# Controle1.net
KiCad netlist of a schematic drawn in Altium Designer
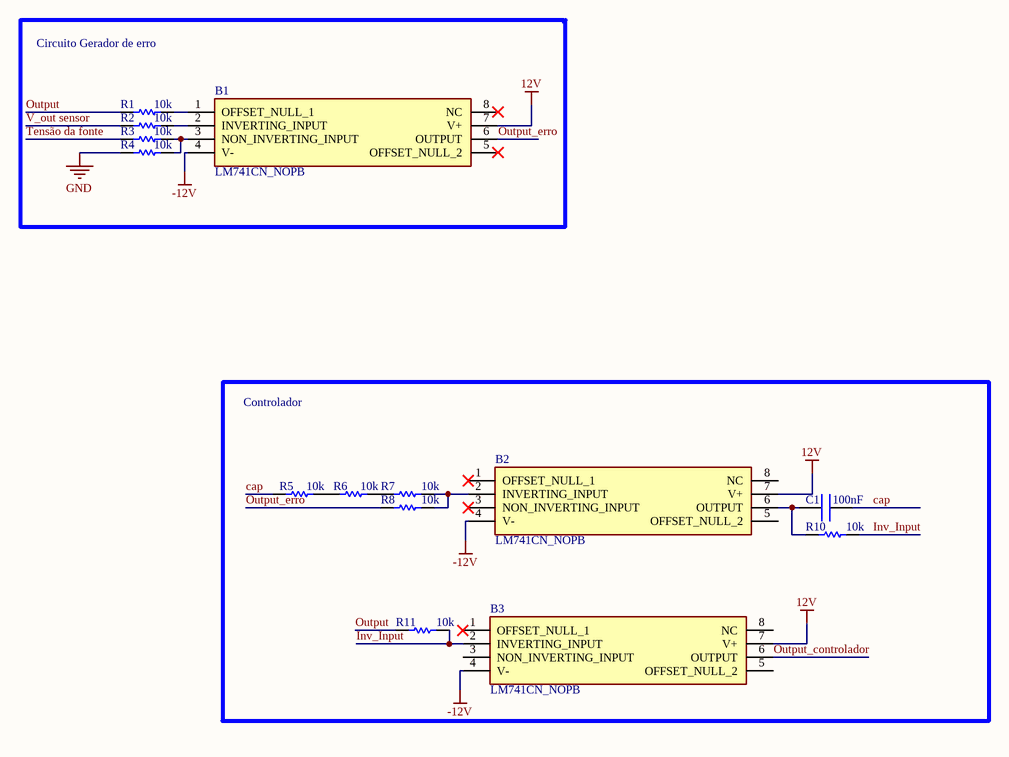
[diagram p0: Controle1.SchDoc]

(export (version "E")
  (design (tool "Eeschema 10.0.6"))
  (components
    (comp (ref "B1")
      (value "LM741CN_NOPB")
      (footprint "DIP794W53P254L959H508Q8N")
      (description "LM741 Operational Amplifier 1MHz DIP8 Texas Instruments LM741CN/NOPB Op Amp, 1MHz, 8-Pin MDIP")
      (fields
        (field (name "MOUSER PART NUMBER") "926-LM741CN/NOPB")
        (field (name "MANUFACTURER_PART_NUMBER") "LM741CN/NOPB")
      )
      (libsource (lib "altium-import") (part "root_0_LM741CN_NOPB_"))
    )
    (comp (ref "B2")
      (value "LM741CN_NOPB")
      (footprint "DIP794W53P254L959H508Q8N")
      (description "LM741 Operational Amplifier 1MHz DIP8 Texas Instruments LM741CN/NOPB Op Amp, 1MHz, 8-Pin MDIP")
      (fields
        (field (name "MOUSER PART NUMBER") "926-LM741CN/NOPB")
        (field (name "MANUFACTURER_PART_NUMBER") "LM741CN/NOPB")
      )
      (libsource (lib "altium-import") (part "root_0_LM741CN_NOPB_"))
    )
    (comp (ref "B3")
      (value "LM741CN_NOPB")
      (footprint "DIP794W53P254L959H508Q8N")
      (description "LM741 Operational Amplifier 1MHz DIP8 Texas Instruments LM741CN/NOPB Op Amp, 1MHz, 8-Pin MDIP")
      (fields
        (field (name "MOUSER PART NUMBER") "926-LM741CN/NOPB")
        (field (name "MANUFACTURER_PART_NUMBER") "LM741CN/NOPB")
      )
      (libsource (lib "altium-import") (part "root_0_LM741CN_NOPB_"))
    )
    (comp (ref "C1")
      (value "100nF")
      (footprint "C0805")
      (description "Cap Ceramic 0.1uF 25V X7R 20% SMD 0805 125°C Paper T/R")
      (fields
        (field (name "MANUFACTURER") "KEMET")
        (field (name "MANUFACTURER PART NUMBER") "C0805C104M3RACTU")
      )
      (libsource (lib "altium-import") (part "root_0_C0805C104M3RACTU_"))
    )
    (comp (ref "R1")
      (value "10k")
      (footprint "RESAD1075W45L335D185")
      (fields
        (field (name "MANUFACTURER") "Yageo")
        (field (name "MANUFACTURER PART NUMBER") "RC0603FR-0710KL")
        (field (name "TOLERANCE") "1%")
      )
      (libsource (lib "altium-import") (part "root_0_MF1/4CL1002F_"))
    )
    (comp (ref "R2")
      (value "10k")
      (footprint "RESAD1075W45L335D185")
      (fields
        (field (name "MANUFACTURER") "Yageo")
        (field (name "MANUFACTURER PART NUMBER") "RC0603FR-0710KL")
        (field (name "TOLERANCE") "1%")
      )
      (libsource (lib "altium-import") (part "root_0_MF1/4CL1002F_"))
    )
    (comp (ref "R3")
      (value "10k")
      (footprint "RESAD1075W45L335D185")
      (fields
        (field (name "MANUFACTURER") "Yageo")
        (field (name "MANUFACTURER PART NUMBER") "RC0603FR-0710KL")
        (field (name "TOLERANCE") "1%")
      )
      (libsource (lib "altium-import") (part "root_0_MF1/4CL1002F_"))
    )
    (comp (ref "R4")
      (value "10k")
      (footprint "RESAD1075W45L335D185")
      (fields
        (field (name "MANUFACTURER") "Yageo")
        (field (name "MANUFACTURER PART NUMBER") "RC0603FR-0710KL")
        (field (name "TOLERANCE") "1%")
      )
      (libsource (lib "altium-import") (part "root_0_MF1/4CL1002F_"))
    )
    (comp (ref "R5")
      (value "10k")
      (footprint "RESAD1075W45L335D185")
      (fields
        (field (name "MANUFACTURER") "Yageo")
        (field (name "MANUFACTURER PART NUMBER") "RC0603FR-0710KL")
        (field (name "TOLERANCE") "1%")
      )
      (libsource (lib "altium-import") (part "root_0_MF1/4CL1002F_"))
    )
    (comp (ref "R6")
      (value "10k")
      (footprint "RESAD1075W45L335D185")
      (fields
        (field (name "MANUFACTURER") "Yageo")
        (field (name "MANUFACTURER PART NUMBER") "RC0603FR-0710KL")
        (field (name "TOLERANCE") "1%")
      )
      (libsource (lib "altium-import") (part "root_0_MF1/4CL1002F_"))
    )
    (comp (ref "R7")
      (value "10k")
      (footprint "RESAD1075W45L335D185")
      (fields
        (field (name "MANUFACTURER") "Yageo")
        (field (name "MANUFACTURER PART NUMBER") "RC0603FR-0710KL")
        (field (name "TOLERANCE") "1%")
      )
      (libsource (lib "altium-import") (part "root_0_MF1/4CL1002F_"))
    )
    (comp (ref "R8")
      (value "10k")
      (footprint "RESAD1075W45L335D185")
      (fields
        (field (name "MANUFACTURER") "Yageo")
        (field (name "MANUFACTURER PART NUMBER") "RC0603FR-0710KL")
        (field (name "TOLERANCE") "1%")
      )
      (libsource (lib "altium-import") (part "root_0_MF1/4CL1002F_"))
    )
    (comp (ref "R10")
      (value "10k")
      (footprint "RESAD1075W45L335D185")
      (fields
        (field (name "MANUFACTURER") "Yageo")
        (field (name "MANUFACTURER PART NUMBER") "RC0603FR-0710KL")
        (field (name "TOLERANCE") "1%")
      )
      (libsource (lib "altium-import") (part "root_0_MF1/4CL1002F_"))
    )
    (comp (ref "R11")
      (value "10k")
      (footprint "RESAD1075W45L335D185")
      (fields
        (field (name "MANUFACTURER") "Yageo")
        (field (name "MANUFACTURER PART NUMBER") "RC0603FR-0710KL")
        (field (name "TOLERANCE") "1%")
      )
      (libsource (lib "altium-import") (part "root_0_MF1/4CL1002F_"))
    )
  )
  (nets
    (net (code "1") (name "-12V") (class "Default")
      (node (ref "B1") (pin "4") (pinfunction "V-_4") (pintype "passive"))
      (node (ref "B2") (pin "4") (pinfunction "V-_4") (pintype "passive"))
      (node (ref "B3") (pin "4") (pinfunction "V-_4") (pintype "passive"))
    )
    (net (code "2") (name "/Inv_Input") (class "Default")
      (node (ref "B3") (pin "2") (pinfunction "INVERTING_INPUT_2") (pintype "passive"))
      (node (ref "R10") (pin "2") (pinfunction "2_2") (pintype "passive"))
      (node (ref "R11") (pin "2") (pinfunction "2_2") (pintype "passive"))
    )
    (net (code "3") (name "/Output") (class "Default")
      (node (ref "R1") (pin "1") (pinfunction "1_1") (pintype "passive"))
      (node (ref "R11") (pin "1") (pinfunction "1_1") (pintype "passive"))
    )
    (net (code "4") (name "/Output_controlador") (class "Default")
      (node (ref "B3") (pin "6") (pinfunction "OUTPUT_6") (pintype "passive"))
    )
    (net (code "5") (name "/Output_erro") (class "Default")
      (node (ref "B1") (pin "6") (pinfunction "OUTPUT_6") (pintype "passive"))
      (node (ref "R8") (pin "1") (pinfunction "1_1") (pintype "passive"))
    )
    (net (code "6") (name "/Tensão da fonte") (class "Default")
      (node (ref "R3") (pin "1") (pinfunction "1_1") (pintype "passive"))
    )
    (net (code "7") (name "/V_out sensor") (class "Default")
      (node (ref "R2") (pin "1") (pinfunction "1_1") (pintype "passive"))
    )
    (net (code "8") (name "/cap") (class "Default")
      (node (ref "C1") (pin "2") (pinfunction "2_2") (pintype "passive"))
      (node (ref "R5") (pin "1") (pinfunction "1_1") (pintype "passive"))
    )
    (net (code "9") (name "12V") (class "Default")
      (node (ref "B1") (pin "7") (pinfunction "V+_7") (pintype "passive"))
      (node (ref "B2") (pin "7") (pinfunction "V+_7") (pintype "passive"))
      (node (ref "B3") (pin "7") (pinfunction "V+_7") (pintype "passive"))
    )
    (net (code "10") (name "GND") (class "Default")
      (node (ref "R4") (pin "1") (pinfunction "1_1") (pintype "passive"))
    )
    (net (code "11") (name "Net-(B1-INVERTING_INPUT)") (class "Default")
      (node (ref "B1") (pin "2") (pinfunction "INVERTING_INPUT_2") (pintype "passive"))
      (node (ref "R2") (pin "2") (pinfunction "2_2") (pintype "passive"))
    )
    (net (code "12") (name "Net-(B1-NON_INVERTING_INPUT)") (class "Default")
      (node (ref "B1") (pin "3") (pinfunction "NON_INVERTING_INPUT_3") (pintype "passive"))
      (node (ref "R3") (pin "2") (pinfunction "2_2") (pintype "passive"))
      (node (ref "R4") (pin "2") (pinfunction "2_2") (pintype "passive"))
    )
    (net (code "13") (name "Net-(B1-OFFSET_NULL_1)") (class "Default")
      (node (ref "B1") (pin "1") (pinfunction "OFFSET_NULL_1_1") (pintype "passive"))
      (node (ref "R1") (pin "2") (pinfunction "2_2") (pintype "passive"))
    )
    (net (code "14") (name "Net-(B2-INVERTING_INPUT)") (class "Default")
      (node (ref "B2") (pin "2") (pinfunction "INVERTING_INPUT_2") (pintype "passive"))
      (node (ref "R7") (pin "2") (pinfunction "2_2") (pintype "passive"))
      (node (ref "R8") (pin "2") (pinfunction "2_2") (pintype "passive"))
    )
    (net (code "15") (name "Net-(B2-OUTPUT)") (class "Default")
      (node (ref "B2") (pin "6") (pinfunction "OUTPUT_6") (pintype "passive"))
      (node (ref "C1") (pin "1") (pinfunction "1_1") (pintype "passive"))
      (node (ref "R10") (pin "1") (pinfunction "1_1") (pintype "passive"))
    )
    (net (code "16") (name "Net-(R5-Pad2)") (class "Default")
      (node (ref "R5") (pin "2") (pinfunction "2_2") (pintype "passive"))
      (node (ref "R6") (pin "1") (pinfunction "1_1") (pintype "passive"))
    )
    (net (code "17") (name "Net-(R6-Pad2)") (class "Default")
      (node (ref "R6") (pin "2") (pinfunction "2_2") (pintype "passive"))
      (node (ref "R7") (pin "1") (pinfunction "1_1") (pintype "passive"))
    )
    (net (code "18") (name "unconnected-(B1-NC-Pad8)") (class "Default")
      (node (ref "B1") (pin "8") (pinfunction "NC_8") (pintype "passive+no_connect"))
    )
    (net (code "19") (name "unconnected-(B1-OFFSET_NULL_2-Pad5)") (class "Default")
      (node (ref "B1") (pin "5") (pinfunction "OFFSET_NULL_2_5") (pintype "passive+no_connect"))
    )
    (net (code "20") (name "unconnected-(B2-NC-Pad8)") (class "Default")
      (node (ref "B2") (pin "8") (pinfunction "NC_8") (pintype "passive"))
    )
    (net (code "21") (name "unconnected-(B2-NON_INVERTING_INPUT-Pad3)") (class "Default")
      (node (ref "B2") (pin "3") (pinfunction "NON_INVERTING_INPUT_3") (pintype "passive+no_connect"))
    )
    (net (code "22") (name "unconnected-(B2-OFFSET_NULL_1-Pad1)") (class "Default")
      (node (ref "B2") (pin "1") (pinfunction "OFFSET_NULL_1_1") (pintype "passive+no_connect"))
    )
    (net (code "23") (name "unconnected-(B2-OFFSET_NULL_2-Pad5)") (class "Default")
      (node (ref "B2") (pin "5") (pinfunction "OFFSET_NULL_2_5") (pintype "passive"))
    )
    (net (code "24") (name "unconnected-(B3-NC-Pad8)") (class "Default")
      (node (ref "B3") (pin "8") (pinfunction "NC_8") (pintype "passive"))
    )
    (net (code "25") (name "unconnected-(B3-NON_INVERTING_INPUT-Pad3)") (class "Default")
      (node (ref "B3") (pin "3") (pinfunction "NON_INVERTING_INPUT_3") (pintype "passive"))
    )
    (net (code "26") (name "unconnected-(B3-OFFSET_NULL_1-Pad1)") (class "Default")
      (node (ref "B3") (pin "1") (pinfunction "OFFSET_NULL_1_1") (pintype "passive+no_connect"))
    )
    (net (code "27") (name "unconnected-(B3-OFFSET_NULL_2-Pad5)") (class "Default")
      (node (ref "B3") (pin "5") (pinfunction "OFFSET_NULL_2_5") (pintype "passive"))
    )
  )
)
